# Power.net
KiCad netlist of a schematic drawn in Altium Designer
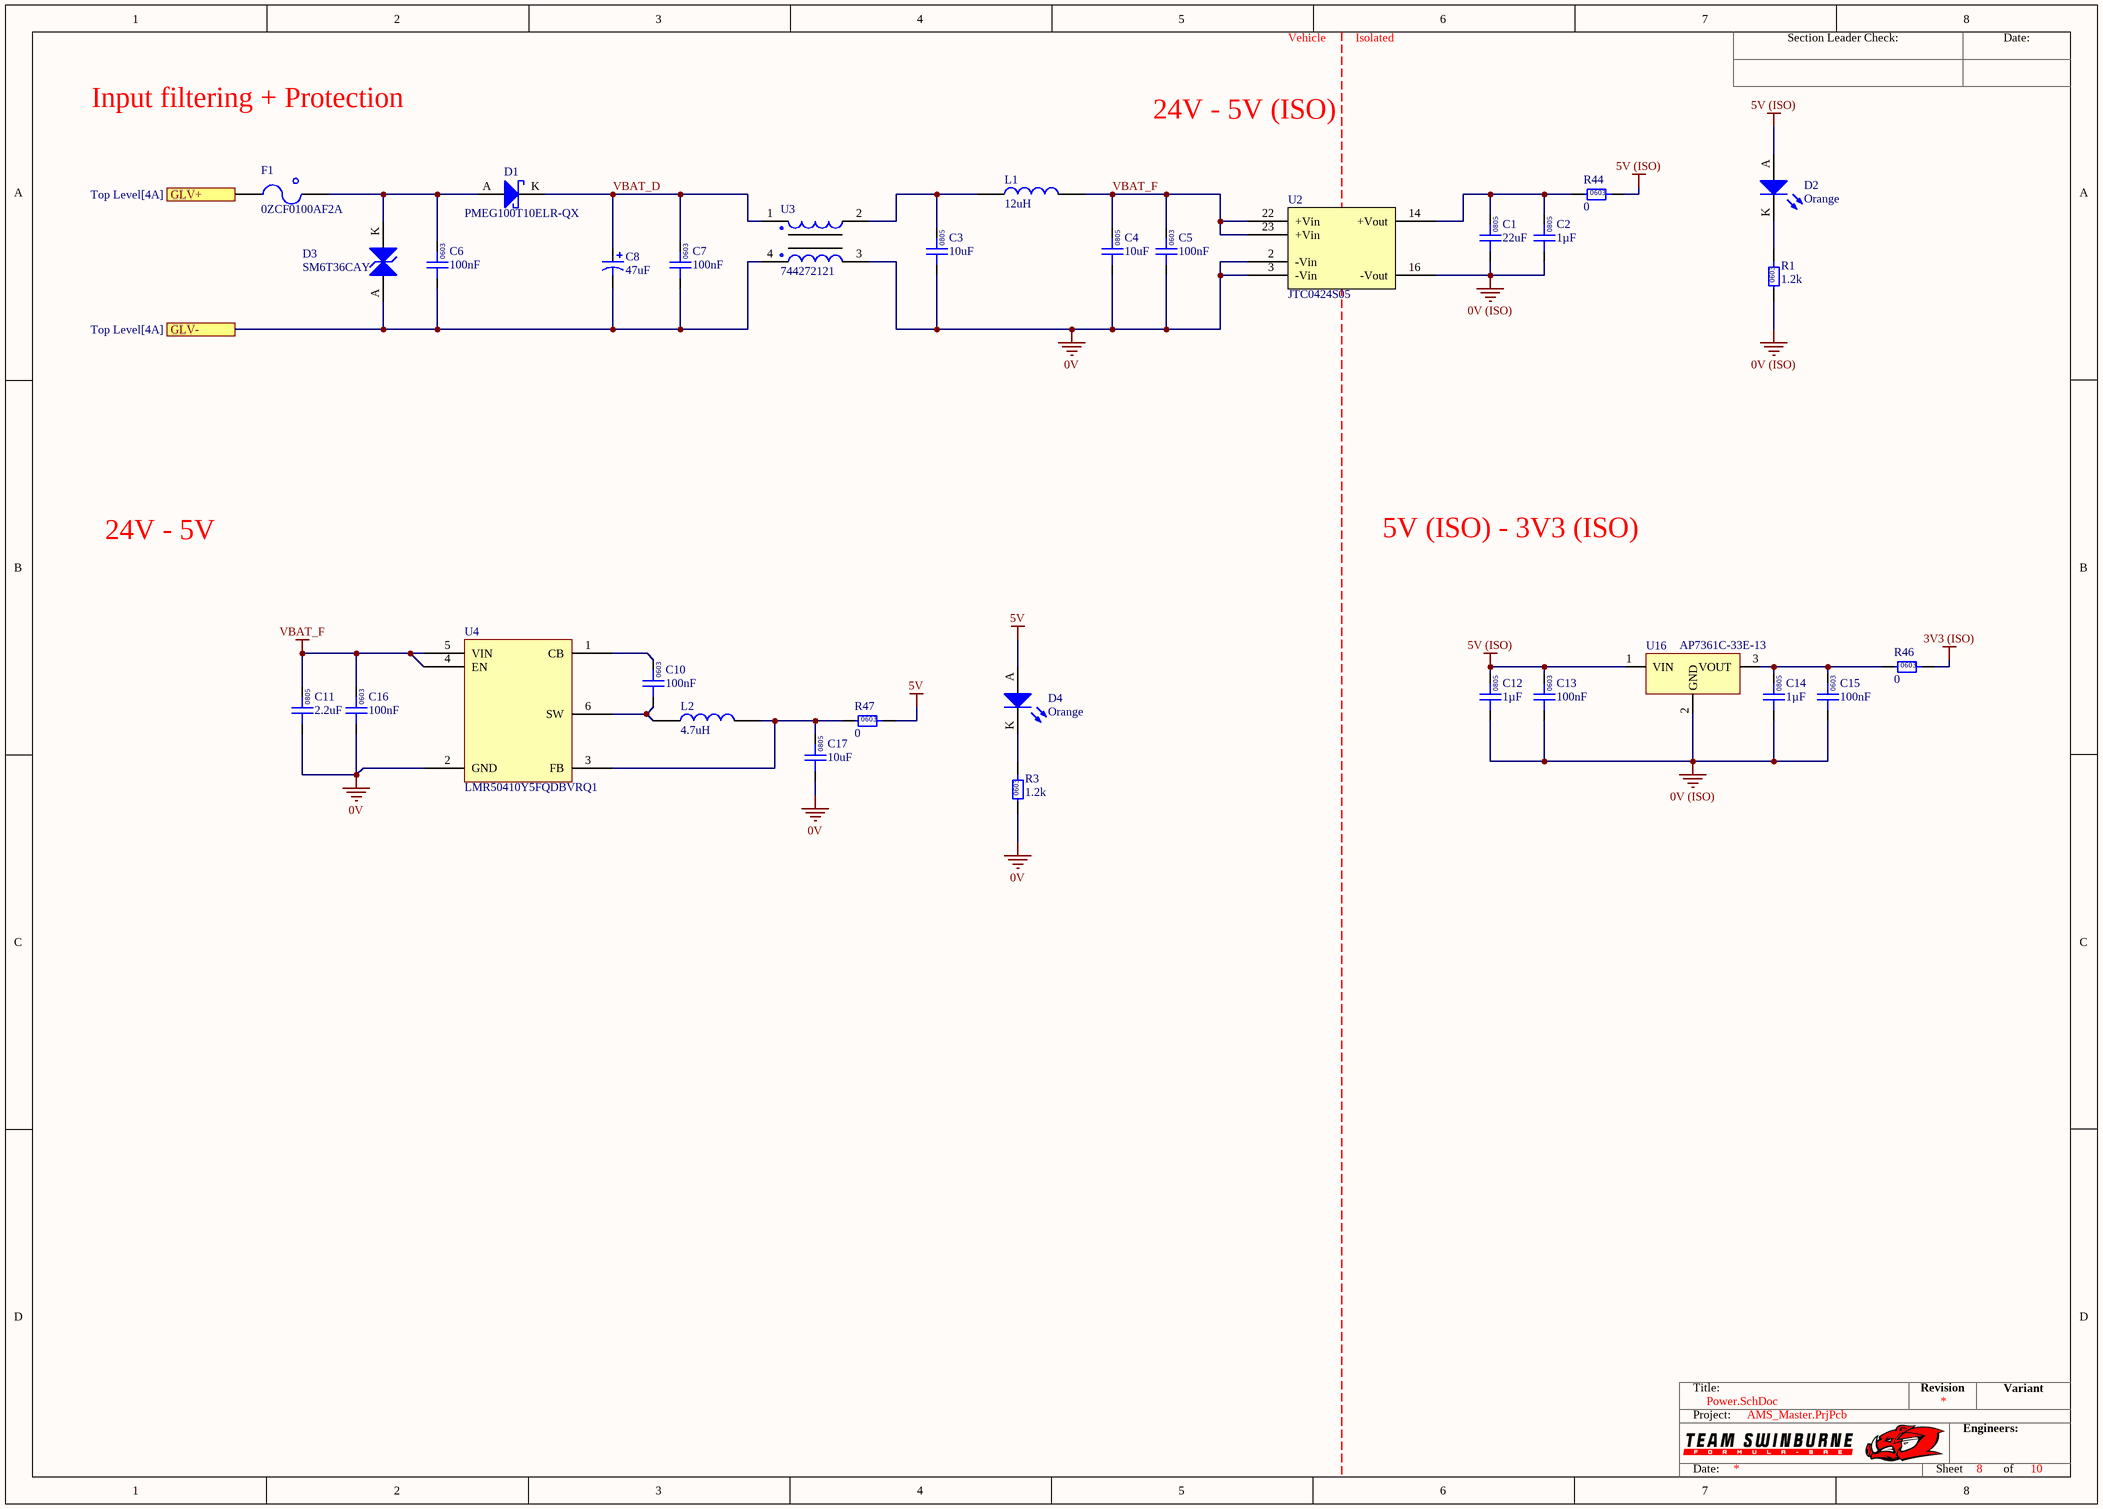
[diagram p0: Power.SchDoc]

(export (version "E")
  (design (tool "Eeschema 10.0.6"))
  (components
    (comp (ref "C1")
      (value "22uF")
      (footprint "0805")
      (fields
        (field (name "PART NUMBER") "GRM21BR61A226ME51L")
        (field (name "MANUFACTURER") "muRata")
        (field (name "TOLERANCE") "20%")
      )
      (libsource (lib "ts_standard_library") (part "Capacitor 0805"))
    )
    (comp (ref "C2")
      (value "1µF")
      (footprint "0805")
      (fields
        (field (name "PART NUMBER") "GCM21BR71H105KA03L")
        (field (name "MANUFACTURER") "muRata")
        (field (name "TOLERANCE") "±10%")
      )
      (libsource (lib "ts_standard_library") (part "Capacitor 0805"))
    )
    (comp (ref "C3")
      (value "10uF")
      (footprint "0805")
      (fields
        (field (name "PART NUMBER") "GRM21BR6YA106KE43L")
        (field (name "MANUFACTURER") "muRata")
        (field (name "TOLERANCE") "10%")
      )
      (libsource (lib "ts_standard_library") (part "Capacitor 0805"))
    )
    (comp (ref "C4")
      (value "10uF")
      (footprint "0805")
      (fields
        (field (name "PART NUMBER") "GRM21BR6YA106KE43L")
        (field (name "MANUFACTURER") "muRata")
        (field (name "TOLERANCE") "10%")
      )
      (libsource (lib "ts_standard_library") (part "Capacitor 0805"))
    )
    (comp (ref "C5")
      (value "100nF")
      (footprint "0603")
      (fields
        (field (name "PART NUMBER") "GCM188L81H104KA57D")
        (field (name "MANUFACTURER") "muRata")
        (field (name "TOLERANCE") "±10%")
      )
      (libsource (lib "ts_standard_library") (part "Capacitor 0603"))
    )
    (comp (ref "C6")
      (value "100nF")
      (footprint "0603")
      (fields
        (field (name "PART NUMBER") "GCM188L81H104KA57D")
        (field (name "MANUFACTURER") "muRata")
        (field (name "TOLERANCE") "±10%")
      )
      (libsource (lib "ts_standard_library") (part "Capacitor 0603"))
    )
    (comp (ref "C7")
      (value "100nF")
      (footprint "0603")
      (fields
        (field (name "PART NUMBER") "GCM188L81H104KA57D")
        (field (name "MANUFACTURER") "muRata")
        (field (name "TOLERANCE") "±10%")
      )
      (libsource (lib "ts_standard_library") (part "Capacitor 0603"))
    )
    (comp (ref "C8")
      (value "~")
      (footprint "CHEMI-CON ELCO")
      (fields
        (field (name "PART NUMBER") "HHXA350ARA470MF61G")
        (field (name "MANUFACTURER") "Chemi-Con")
        (field (name "TOLERANCE") "20%")
      )
      (libsource (lib "ts_standard_library") (part "Capacitor (Polarised)"))
    )
    (comp (ref "C10")
      (value "100nF")
      (footprint "0603")
      (fields
        (field (name "PART NUMBER") "GCM188L81H104KA57D")
        (field (name "MANUFACTURER") "muRata")
        (field (name "TOLERANCE") "±10%")
      )
      (libsource (lib "ts_standard_library") (part "Capacitor 0603"))
    )
    (comp (ref "C11")
      (value "2.2uF")
      (footprint "0805")
      (fields
        (field (name "PART NUMBER") "GRM21BR71E225KE11L")
        (field (name "MANUFACTURER") "Murata Electronics")
        (field (name "TOLERANCE") "±10%")
      )
      (libsource (lib "ts_standard_library") (part "Capacitor 0805"))
    )
    (comp (ref "C12")
      (value "1µF")
      (footprint "0805")
      (fields
        (field (name "PART NUMBER") "GCM21BR71H105KA03L")
        (field (name "MANUFACTURER") "muRata")
        (field (name "TOLERANCE") "±10%")
      )
      (libsource (lib "ts_standard_library") (part "Capacitor 0805"))
    )
    (comp (ref "C13")
      (value "100nF")
      (footprint "0603")
      (fields
        (field (name "PART NUMBER") "GCM188L81H104KA57D")
        (field (name "MANUFACTURER") "muRata")
        (field (name "TOLERANCE") "±10%")
      )
      (libsource (lib "ts_standard_library") (part "Capacitor 0603"))
    )
    (comp (ref "C14")
      (value "1µF")
      (footprint "0805")
      (fields
        (field (name "PART NUMBER") "GCM21BR71H105KA03L")
        (field (name "MANUFACTURER") "muRata")
        (field (name "TOLERANCE") "±10%")
      )
      (libsource (lib "ts_standard_library") (part "Capacitor 0805"))
    )
    (comp (ref "C15")
      (value "100nF")
      (footprint "0603")
      (fields
        (field (name "PART NUMBER") "GCM188L81H104KA57D")
        (field (name "MANUFACTURER") "muRata")
        (field (name "TOLERANCE") "±10%")
      )
      (libsource (lib "ts_standard_library") (part "Capacitor 0603"))
    )
    (comp (ref "C16")
      (value "100nF")
      (footprint "0603")
      (fields
        (field (name "PART NUMBER") "GCM188L81H104KA57D")
        (field (name "MANUFACTURER") "muRata")
        (field (name "TOLERANCE") "±10%")
      )
      (libsource (lib "ts_standard_library") (part "Capacitor 0603"))
    )
    (comp (ref "C17")
      (value "10uF")
      (footprint "0805")
      (fields
        (field (name "PART NUMBER") "GRM21BR6YA106KE43L")
        (field (name "MANUFACTURER") "muRata")
        (field (name "TOLERANCE") "10%")
      )
      (libsource (lib "ts_standard_library") (part "Capacitor 0805"))
    )
    (comp (ref "D1")
      (value "PMEG100T10ELR-QX")
      (footprint "NXP SOD123W")
      (fields
        (field (name "MANUFACTURER") "Nexperia USA Inc.")
        (field (name "DIGIKEY PART NUMBER") "1727-PMEG100T10ELR-QXCT-ND")
      )
      (libsource (lib "ts_standard_library") (part "Diode (Schottky)"))
    )
    (comp (ref "D2")
      (value "Orange")
      (footprint "0805 LED")
      (description "Orange LED Indication - Discrete 1.75V 0805 (2012 Metric)")
      (fields (field (name "PART NUMBER") "SML-211DTT86") (field (name "MANUFACTURER") "ROHM Semiconductor"))
      (libsource (lib "ts_standard_library") (part "LED"))
    )
    (comp (ref "D3")
      (value "SM6T36CAY")
      (footprint "ST SMB DIODE")
      (fields
        (field (name "MANUFACTURER") "STMicroelectronics")
        (field (name "DIGIKEY PART NUMBER") "497-10804-1-ND")
      )
      (libsource (lib "ts_standard_library") (part "TVS (Bidirectional)"))
    )
    (comp (ref "D4")
      (value "Orange")
      (footprint "0805 LED")
      (description "Orange LED Indication - Discrete 1.75V 0805 (2012 Metric)")
      (fields (field (name "PART NUMBER") "SML-211DTT86") (field (name "MANUFACTURER") "ROHM Semiconductor"))
      (libsource (lib "ts_standard_library") (part "LED"))
    )
    (comp (ref "F1")
      (value "0ZCF0100AF2A")
      (footprint "2920")
      (description "PTC RESET FUSE 60V 1A 292")
      (fields
        (field (name "MANUFACTURER") "Littelfuse Inc.")
        (field (name "DIGIKEY PART NUMBER") "507-2070-1-ND")
      )
      (libsource (lib "ts_standard_library") (part "PTC Fuse"))
    )
    (comp (ref "L1")
      (value "12uH")
      (footprint "1812")
      (fields
        (field (name "PART NUMBER") "RLS-126")
        (field (name "MANUFACTURER") "Recom")
        (field (name "TOLERANCE") "0.2")
      )
      (libsource (lib "ts_standard_library") (part "Inductor"))
    )
    (comp (ref "L2")
      (value "4.7uH")
      (footprint "SRN3015TA-4R7M")
      (fields
        (field (name "PART NUMBER") "SRN4018-4R7M")
        (field (name "MANUFACTURER") "Bourns")
        (field (name "TOLERANCE") "0.2")
      )
      (libsource (lib "ts_standard_library") (part "Inductor"))
    )
    (comp (ref "R1")
      (value "1.2k")
      (footprint "0603")
      (fields
        (field (name "PART NUMBER") "RC0603JR-071K2L")
        (field (name "MANUFACTURER") "YAGEO")
        (field (name "TOLERANCE") "0.01")
      )
      (libsource (lib "ts_standard_library") (part "Resistor 0603"))
    )
    (comp (ref "R3")
      (value "1.2k")
      (footprint "0603")
      (fields
        (field (name "PART NUMBER") "RC0603JR-071K2L")
        (field (name "MANUFACTURER") "YAGEO")
        (field (name "TOLERANCE") "0.01")
      )
      (libsource (lib "ts_standard_library") (part "Resistor 0603"))
    )
    (comp (ref "R44")
      (value "0")
      (footprint "0603")
      (fields
        (field (name "PART NUMBER") "RC0603JR-070RL")
        (field (name "MANUFACTURER") "YAGEO")
        (field (name "TOLERANCE") "0.01")
      )
      (libsource (lib "ts_standard_library") (part "Resistor 0603"))
    )
    (comp (ref "R46")
      (value "0")
      (footprint "0603")
      (fields
        (field (name "PART NUMBER") "RC0603JR-070RL")
        (field (name "MANUFACTURER") "YAGEO")
        (field (name "TOLERANCE") "0.01")
      )
      (libsource (lib "ts_standard_library") (part "Resistor 0603"))
    )
    (comp (ref "R47")
      (value "0")
      (footprint "0603")
      (fields
        (field (name "PART NUMBER") "RC0603JR-070RL")
        (field (name "MANUFACTURER") "YAGEO")
        (field (name "TOLERANCE") "0.01")
      )
      (libsource (lib "ts_standard_library") (part "Resistor 0603"))
    )
    (comp (ref "U2")
      (value "JTC0424S05")
      (footprint "24-DIP Module, 7 Leads")
      (description "DC DC CONVERTER 5V 4W")
      (fields (field (name "MANUFACTURER") "XP Power") (field (name "DIGIKEY PART NUMBER") "JTC0424S05-ND"))
      (libsource (lib "ts_20-standard-library") (part "JTC0424S05"))
    )
    (comp (ref "U3")
      (value "744272121")
      (footprint "Wurth 4-PC Pad")
      (fields
        (field (name "MANUFACTURER") "Wurth Electronics Inc")
        (field (name "DIGIKEY PART NUMBER") "732-1489-1-ND")
      )
      (libsource (lib "ts_standard_library") (part "CM Choke"))
    )
    (comp (ref "U4")
      (value "LMR50410Y5FQDBVRQ1")
      (footprint "TI-SOT23-6")
      (description "IC REG BUCK 5V 1A SOT23-6")
      (fields (field (name "PART NUMBER") "LMR50410-Q1") (field (name "MANUFACTURER") "Texas Instruments"))
      (libsource (lib "ts_standard_library") (part "LMR50410Y5FQDBVRQ1"))
    )
    (comp (ref "U16")
      (value "AP7361C-33E-13")
      (footprint "DI SOT-223")
      (description "IC REG LINEAR 3.3V 1A SOT223")
      (fields
        (field (name "MANUFACTURER") "Diodes Incorporated")
        (field (name "DIGIKEY PART NUMBER") "AP7361C-33E-13DICT-ND")
      )
      (libsource (lib "ts_standard_library") (part "AP7361C-33E-13"))
    )
  )
  (nets
    (net (code "1") (name "/GLV+") (class "Default")
      (node (ref "F1") (pin "1") (pinfunction "1_1") (pintype "passive"))
    )
    (net (code "2") (name "/GLV-") (class "Default")
      (node (ref "C6") (pin "1") (pinfunction "1_1") (pintype "passive"))
      (node (ref "C7") (pin "1") (pinfunction "1_1") (pintype "passive"))
      (node (ref "C8") (pin "1") (pinfunction "1_1") (pintype "passive"))
      (node (ref "D3") (pin "A") (pinfunction "A_A") (pintype "passive"))
      (node (ref "U3") (pin "4") (pinfunction "4_4") (pintype "passive"))
    )
    (net (code "3") (name "/VBAT_D") (class "Default")
      (node (ref "C7") (pin "2") (pinfunction "2_2") (pintype "passive"))
      (node (ref "C8") (pin "2") (pinfunction "2_2") (pintype "passive"))
      (node (ref "D1") (pin "K") (pinfunction "K_K") (pintype "passive"))
      (node (ref "U3") (pin "1") (pinfunction "1_1") (pintype "passive"))
    )
    (net (code "4") (name "0V") (class "Default")
      (node (ref "C11") (pin "1") (pinfunction "1_1") (pintype "passive"))
      (node (ref "C16") (pin "1") (pinfunction "1_1") (pintype "passive"))
      (node (ref "C17") (pin "1") (pinfunction "1_1") (pintype "passive"))
      (node (ref "C3") (pin "1") (pinfunction "1_1") (pintype "passive"))
      (node (ref "C4") (pin "1") (pinfunction "1_1") (pintype "passive"))
      (node (ref "C5") (pin "1") (pinfunction "1_1") (pintype "passive"))
      (node (ref "R3") (pin "1") (pinfunction "1_1") (pintype "passive"))
      (node (ref "U2") (pin "2") (pinfunction "-Vin_2") (pintype "passive"))
      (node (ref "U2") (pin "3") (pinfunction "-Vin_3") (pintype "passive"))
      (node (ref "U3") (pin "3") (pinfunction "3_3") (pintype "power_in"))
      (node (ref "U4") (pin "2") (pinfunction "GND_2") (pintype "passive"))
    )
    (net (code "5") (name "0V (ISO)") (class "Default")
      (node (ref "C1") (pin "1") (pinfunction "1_1") (pintype "passive"))
      (node (ref "C12") (pin "1") (pinfunction "1_1") (pintype "passive"))
      (node (ref "C13") (pin "1") (pinfunction "1_1") (pintype "passive"))
      (node (ref "C14") (pin "1") (pinfunction "1_1") (pintype "passive"))
      (node (ref "C15") (pin "1") (pinfunction "1_1") (pintype "passive"))
      (node (ref "C2") (pin "1") (pinfunction "1_1") (pintype "passive"))
      (node (ref "R1") (pin "1") (pinfunction "1_1") (pintype "passive"))
      (node (ref "U16") (pin "2") (pinfunction "GND_2") (pintype "passive"))
      (node (ref "U2") (pin "16") (pinfunction "-Vout_16") (pintype "passive"))
    )
    (net (code "6") (name "3V3 (ISO)") (class "Default")
      (node (ref "R46") (pin "2") (pinfunction "2_2") (pintype "passive"))
    )
    (net (code "7") (name "5V") (class "Default")
      (node (ref "D4") (pin "A") (pinfunction "A_A") (pintype "passive"))
      (node (ref "R47") (pin "2") (pinfunction "2_2") (pintype "passive"))
    )
    (net (code "8") (name "5V (ISO)") (class "Default")
      (node (ref "C12") (pin "2") (pinfunction "2_2") (pintype "passive"))
      (node (ref "C13") (pin "2") (pinfunction "2_2") (pintype "passive"))
      (node (ref "D2") (pin "A") (pinfunction "A_A") (pintype "passive"))
      (node (ref "R44") (pin "2") (pinfunction "2_2") (pintype "passive"))
      (node (ref "U16") (pin "1") (pinfunction "VIN_1") (pintype "passive"))
    )
    (net (code "9") (name "Net-(C3-Pad2)") (class "Default")
      (node (ref "C3") (pin "2") (pinfunction "2_2") (pintype "passive"))
      (node (ref "L1") (pin "2") (pinfunction "2_2") (pintype "passive"))
      (node (ref "U3") (pin "2") (pinfunction "2_2") (pintype "passive"))
    )
    (net (code "10") (name "Net-(C6-Pad2)") (class "Default")
      (node (ref "C6") (pin "2") (pinfunction "2_2") (pintype "passive"))
      (node (ref "D1") (pin "A") (pinfunction "A_A") (pintype "passive"))
      (node (ref "D3") (pin "K") (pinfunction "K_K") (pintype "passive"))
      (node (ref "F1") (pin "2") (pinfunction "2_2") (pintype "passive"))
    )
    (net (code "11") (name "Net-(D2-PadK)") (class "Default")
      (node (ref "D2") (pin "K") (pinfunction "K_K") (pintype "passive"))
      (node (ref "R1") (pin "2") (pinfunction "2_2") (pintype "passive"))
    )
    (net (code "12") (name "Net-(D4-PadK)") (class "Default")
      (node (ref "D4") (pin "K") (pinfunction "K_K") (pintype "passive"))
      (node (ref "R3") (pin "2") (pinfunction "2_2") (pintype "passive"))
    )
    (net (code "13") (name "Net-(U2-+Vout)") (class "Default")
      (node (ref "C1") (pin "2") (pinfunction "2_2") (pintype "passive"))
      (node (ref "C2") (pin "2") (pinfunction "2_2") (pintype "passive"))
      (node (ref "R44") (pin "1") (pinfunction "1_1") (pintype "passive"))
      (node (ref "U2") (pin "14") (pinfunction "+Vout_14") (pintype "passive"))
    )
    (net (code "14") (name "Net-(U4-CB)") (class "Default")
      (node (ref "C10") (pin "2") (pinfunction "2_2") (pintype "passive"))
      (node (ref "U4") (pin "1") (pinfunction "CB_1") (pintype "passive"))
    )
    (net (code "15") (name "Net-(U4-FB)") (class "Default")
      (node (ref "C17") (pin "2") (pinfunction "2_2") (pintype "passive"))
      (node (ref "L2") (pin "1") (pinfunction "1_1") (pintype "passive"))
      (node (ref "R47") (pin "1") (pinfunction "1_1") (pintype "passive"))
      (node (ref "U4") (pin "3") (pinfunction "FB_3") (pintype "passive"))
    )
    (net (code "16") (name "Net-(U4-SW)") (class "Default")
      (node (ref "C10") (pin "1") (pinfunction "1_1") (pintype "passive"))
      (node (ref "L2") (pin "2") (pinfunction "2_2") (pintype "passive"))
      (node (ref "U4") (pin "6") (pinfunction "SW_6") (pintype "passive"))
    )
    (net (code "17") (name "Net-(U16-VOUT)") (class "Default")
      (node (ref "C14") (pin "2") (pinfunction "2_2") (pintype "passive"))
      (node (ref "C15") (pin "2") (pinfunction "2_2") (pintype "passive"))
      (node (ref "R46") (pin "1") (pinfunction "1_1") (pintype "passive"))
      (node (ref "U16") (pin "3") (pinfunction "VOUT_3") (pintype "passive"))
    )
    (net (code "18") (name "VBAT_F") (class "Default")
      (node (ref "C11") (pin "2") (pinfunction "2_2") (pintype "passive"))
      (node (ref "C16") (pin "2") (pinfunction "2_2") (pintype "passive"))
      (node (ref "C4") (pin "2") (pinfunction "2_2") (pintype "passive"))
      (node (ref "C5") (pin "2") (pinfunction "2_2") (pintype "passive"))
      (node (ref "L1") (pin "1") (pinfunction "1_1") (pintype "passive"))
      (node (ref "U2") (pin "22") (pinfunction "+Vin_22") (pintype "passive"))
      (node (ref "U2") (pin "23") (pinfunction "+Vin_23") (pintype "passive"))
      (node (ref "U4") (pin "4") (pinfunction "EN_4") (pintype "passive"))
      (node (ref "U4") (pin "5") (pinfunction "VIN_5") (pintype "passive"))
    )
  )
)
